# ventmon_t0_5e.net
KiCad netlist of a schematic drawn in EAGLE
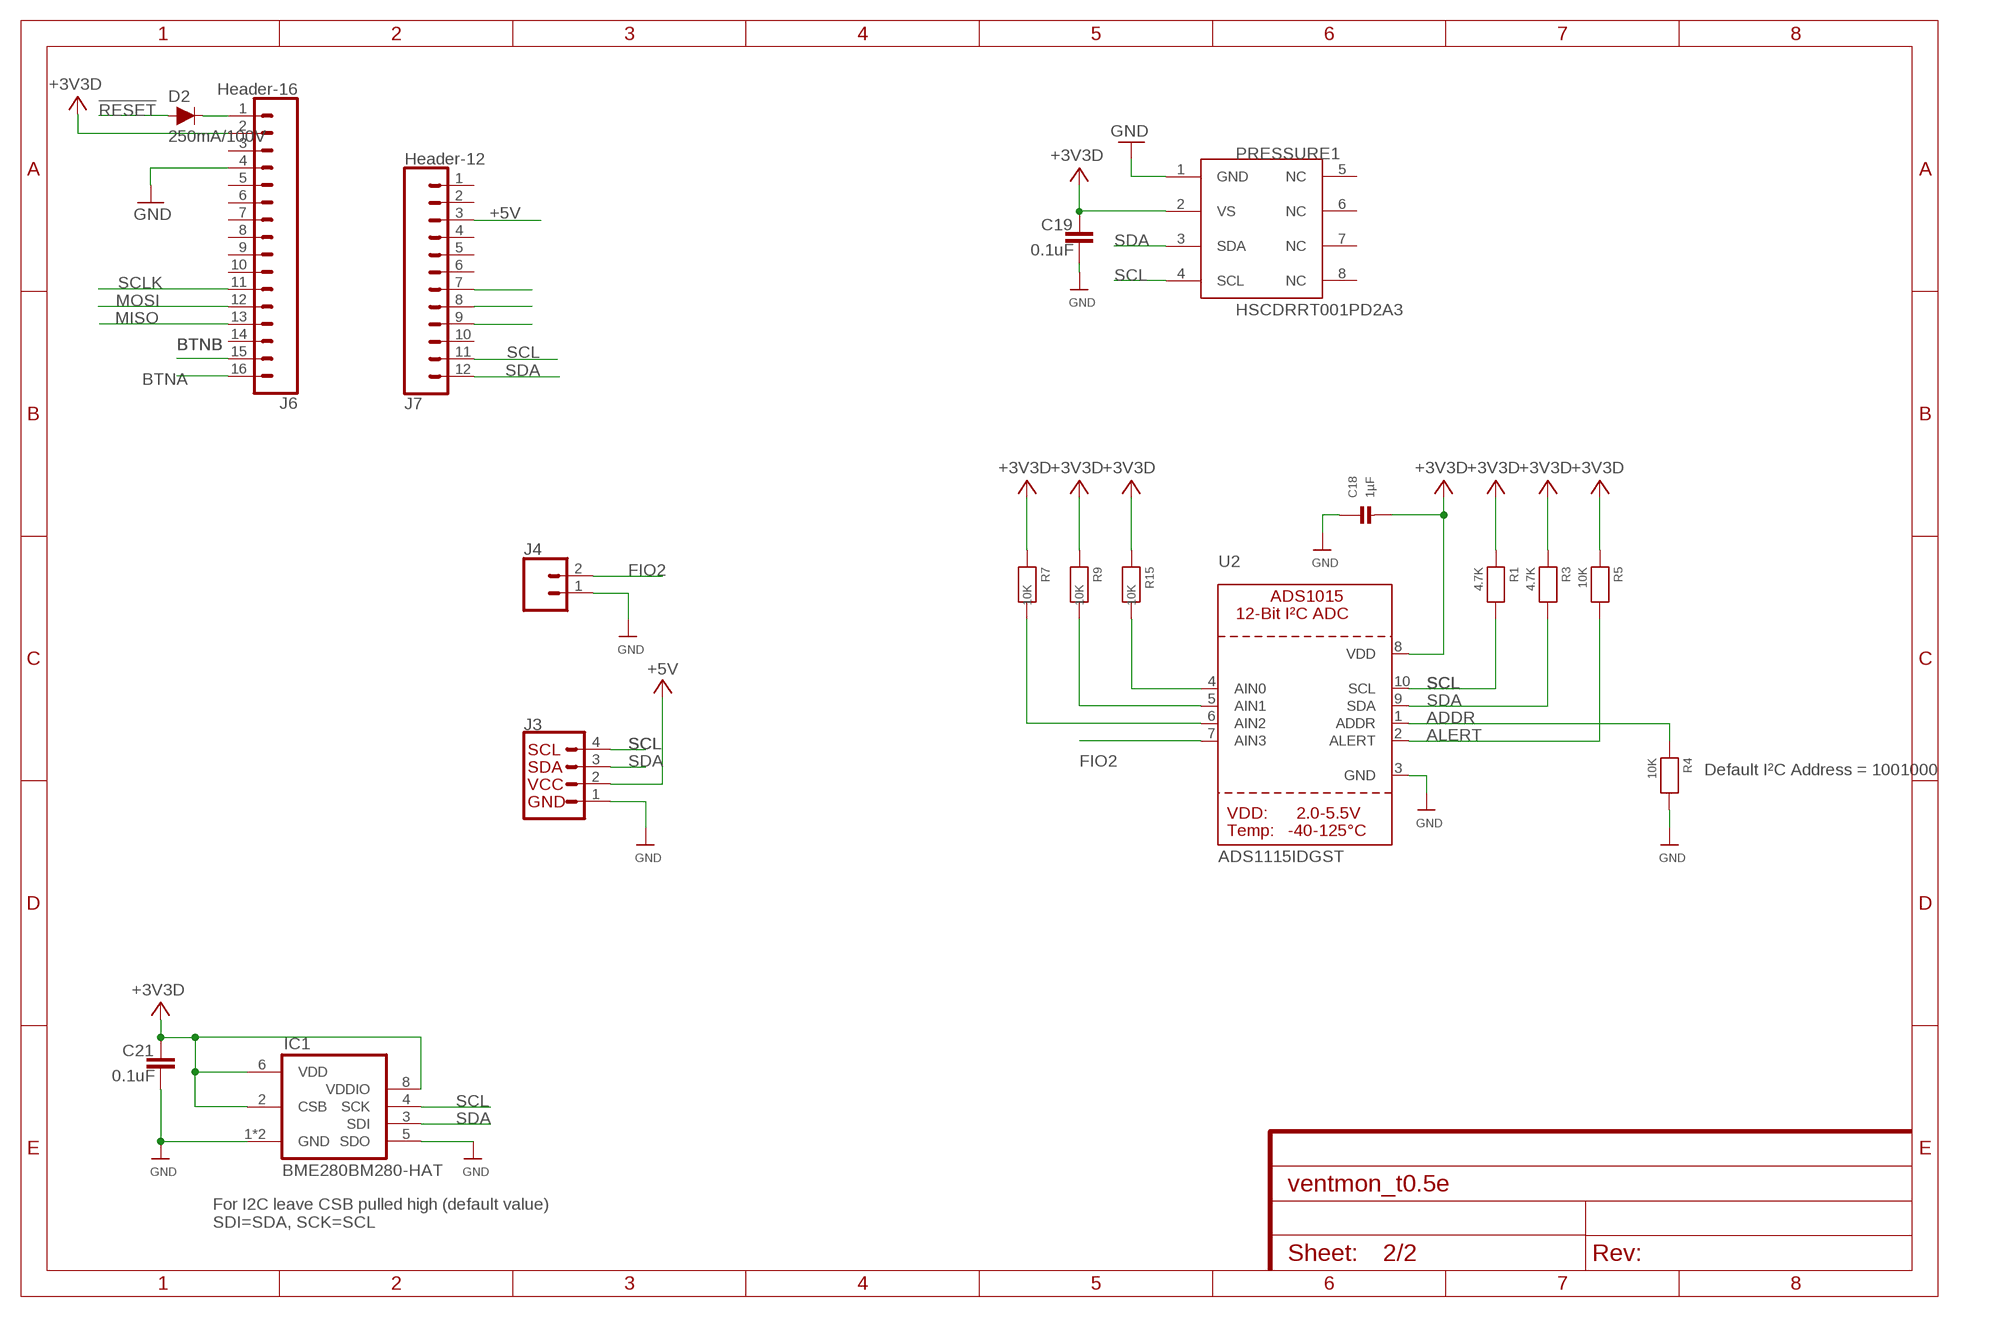
[diagram p0: schematic, sheet 2]

(export (version "E")
  (design (tool "Eeschema 10.0.6"))
  (components
    (comp (ref "C18")
      (value "1µF")
      (footprint "eagle-import:0603")
      (libsource (lib "eagle-import") (part "CAP_CERAMIC0603"))
    )
    (comp (ref "C19")
      (value "0.1uF")
      (footprint "eagle-import:C0402_B")
      (libsource (lib "eagle-import") (part "CAP_1"))
    )
    (comp (ref "C21")
      (value "0.1uF")
      (footprint "eagle-import:C0402_B")
      (libsource (lib "eagle-import") (part "CAP_1"))
    )
    (comp (ref "D2")
      (value "250mA/100V")
      (footprint "eagle-import:SOD-323")
      (libsource (lib "eagle-import") (part "DIODE-BAS16J"))
    )
    (comp (ref "IC1")
      (value "BME280BM280-HAT")
      (footprint "eagle-import:BME280-HAT")
      (libsource (lib "eagle-import") (part "BME280BM280-HAT"))
    )
    (comp (ref "J3")
      (value "QWIIC_CONNECTORJS-1MM")
      (footprint "eagle-import:1X04_1MM_RA")
      (libsource (lib "eagle-import") (part "QWIIC_CONNECTORJS-1MM"))
    )
    (comp (ref "J4")
      (value "CONN_02")
      (footprint "eagle-import:1X02")
      (libsource (lib "eagle-import") (part "CONN_02"))
    )
    (comp (ref "J6")
      (value "Header-16")
      (footprint "eagle-import:1X16")
      (libsource (lib "eagle-import") (part "CONN_16"))
    )
    (comp (ref "J7")
      (value "Header-12")
      (footprint "eagle-import:1X12")
      (libsource (lib "eagle-import") (part "CONN_12"))
    )
    (comp (ref "PRESSURE1")
      (value "HSCDRRT001PD2A3")
      (footprint "eagle-import:DIP1330W46P254L1000H616Q8B")
      (libsource (lib "eagle-import") (part "HSCDRRT001PD2A3"))
    )
    (comp (ref "R1")
      (value "4.7K")
      (footprint "eagle-import:0603")
      (libsource (lib "eagle-import") (part "RESISTOR0603"))
    )
    (comp (ref "R3")
      (value "4.7K")
      (footprint "eagle-import:0603")
      (libsource (lib "eagle-import") (part "RESISTOR0603"))
    )
    (comp (ref "R4")
      (value "10K")
      (footprint "eagle-import:0603")
      (libsource (lib "eagle-import") (part "RESISTOR0603"))
    )
    (comp (ref "R5")
      (value "10K")
      (footprint "eagle-import:0603")
      (libsource (lib "eagle-import") (part "RESISTOR0603"))
    )
    (comp (ref "R7")
      (value "10K")
      (footprint "eagle-import:0603")
      (libsource (lib "eagle-import") (part "RESISTOR0603"))
    )
    (comp (ref "R9")
      (value "10K")
      (footprint "eagle-import:0603")
      (libsource (lib "eagle-import") (part "RESISTOR0603"))
    )
    (comp (ref "R15")
      (value "10K")
      (footprint "eagle-import:0603")
      (libsource (lib "eagle-import") (part "RESISTOR0603"))
    )
    (comp (ref "U2")
      (value "ADS1115IDGST")
      (footprint "eagle-import:MSOP10")
      (libsource (lib "eagle-import") (part "ADC_ADS1015"))
    )
  )
  (nets
    (net (code "1") (name "+3V3") (class "Default")
      (node (ref "C18") (pin "2") (pinfunction "P$2_2") (pintype "passive"))
      (node (ref "C19") (pin "2") (pinfunction "P$2_2") (pintype "passive"))
      (node (ref "C21") (pin "2") (pinfunction "P$2_2") (pintype "passive"))
      (node (ref "IC1") (pin "2") (pinfunction "CSB_2") (pintype "input"))
      (node (ref "IC1") (pin "6") (pinfunction "VDD_6") (pintype "power_in"))
      (node (ref "IC1") (pin "8") (pinfunction "VDDIO_8") (pintype "power_in"))
      (node (ref "J6") (pin "2") (pinfunction "2_2") (pintype "passive"))
      (node (ref "PRESSURE1") (pin "2") (pinfunction "VS_2") (pintype "bidirectional"))
      (node (ref "R1") (pin "1") (pinfunction "1_1") (pintype "passive"))
      (node (ref "R15") (pin "1") (pinfunction "1_1") (pintype "passive"))
      (node (ref "R3") (pin "1") (pinfunction "1_1") (pintype "passive"))
      (node (ref "R5") (pin "1") (pinfunction "1_1") (pintype "passive"))
      (node (ref "R7") (pin "1") (pinfunction "1_1") (pintype "passive"))
      (node (ref "R9") (pin "1") (pinfunction "1_1") (pintype "passive"))
      (node (ref "U2") (pin "8") (pinfunction "VDD_8") (pintype "bidirectional"))
    )
    (net (code "2") (name "+5V") (class "Default")
      (node (ref "J3") (pin "2") (pinfunction "VCC_2") (pintype "power_in"))
      (node (ref "J7") (pin "3") (pinfunction "3_3") (pintype "passive"))
    )
    (net (code "3") (name "ADDR") (class "Default")
      (node (ref "R4") (pin "1") (pinfunction "1_1") (pintype "passive"))
      (node (ref "U2") (pin "1") (pinfunction "ADDR_1") (pintype "bidirectional"))
    )
    (net (code "4") (name "ALERT") (class "Default")
      (node (ref "R5") (pin "2") (pinfunction "2_2") (pintype "passive"))
      (node (ref "U2") (pin "2") (pinfunction "ALERT_2") (pintype "bidirectional"))
    )
    (net (code "5") (name "BTNA") (class "Default")
      (node (ref "J6") (pin "16") (pinfunction "16_16") (pintype "passive"))
    )
    (net (code "6") (name "BTNB") (class "Default")
      (node (ref "J6") (pin "15") (pinfunction "15_15") (pintype "passive"))
    )
    (net (code "7") (name "FIO2") (class "Default")
      (node (ref "J4") (pin "2") (pinfunction "2_2") (pintype "passive"))
      (node (ref "U2") (pin "7") (pinfunction "AIN3_7") (pintype "bidirectional"))
    )
    (net (code "8") (name "GND") (class "Default")
      (node (ref "C18") (pin "1") (pinfunction "P$1_1") (pintype "passive"))
      (node (ref "C19") (pin "1") (pinfunction "P$1_1") (pintype "passive"))
      (node (ref "C21") (pin "1") (pinfunction "P$1_1") (pintype "passive"))
      (node (ref "IC1") (pin "1") (pinfunction "GND_1") (pintype "power_in"))
      (node (ref "IC1") (pin "5") (pinfunction "SDO_5") (pintype "input"))
      (node (ref "IC1") (pin "7") (pinfunction "GND_7") (pintype "power_in"))
      (node (ref "J3") (pin "1") (pinfunction "GND_1") (pintype "power_in"))
      (node (ref "J4") (pin "1") (pinfunction "1_1") (pintype "passive"))
      (node (ref "J6") (pin "4") (pinfunction "4_4") (pintype "passive"))
      (node (ref "PRESSURE1") (pin "1") (pinfunction "GND_1") (pintype "bidirectional"))
      (node (ref "R4") (pin "2") (pinfunction "2_2") (pintype "passive"))
      (node (ref "U2") (pin "3") (pinfunction "GND_3") (pintype "bidirectional"))
    )
    (net (code "9") (name "MISO") (class "Default")
      (node (ref "J6") (pin "13") (pinfunction "13_13") (pintype "passive"))
    )
    (net (code "10") (name "MOSI") (class "Default")
      (node (ref "J6") (pin "12") (pinfunction "12_12") (pintype "passive"))
    )
    (net (code "11") (name "Net-(D2-PadC)") (class "Default")
      (node (ref "D2") (pin "C") (pinfunction "C_C") (pintype "passive"))
      (node (ref "J6") (pin "1") (pinfunction "1_1") (pintype "passive"))
    )
    (net (code "12") (name "Net-(U2-AIN0)") (class "Default")
      (node (ref "R15") (pin "2") (pinfunction "2_2") (pintype "passive"))
      (node (ref "U2") (pin "4") (pinfunction "AIN0_4") (pintype "bidirectional"))
    )
    (net (code "13") (name "Net-(U2-AIN1)") (class "Default")
      (node (ref "R9") (pin "2") (pinfunction "2_2") (pintype "passive"))
      (node (ref "U2") (pin "5") (pinfunction "AIN1_5") (pintype "bidirectional"))
    )
    (net (code "14") (name "Net-(U2-AIN2)") (class "Default")
      (node (ref "R7") (pin "2") (pinfunction "2_2") (pintype "passive"))
      (node (ref "U2") (pin "6") (pinfunction "AIN2_6") (pintype "bidirectional"))
    )
    (net (code "15") (name "SCL") (class "Default")
      (node (ref "IC1") (pin "4") (pinfunction "SCK_4") (pintype "bidirectional"))
      (node (ref "J3") (pin "4") (pinfunction "SCL_4") (pintype "passive"))
      (node (ref "J7") (pin "11") (pinfunction "11_11") (pintype "passive"))
      (node (ref "PRESSURE1") (pin "4") (pinfunction "SCL_4") (pintype "bidirectional"))
      (node (ref "R1") (pin "2") (pinfunction "2_2") (pintype "passive"))
      (node (ref "U2") (pin "10") (pinfunction "SCL_10") (pintype "bidirectional"))
    )
    (net (code "16") (name "SCLK") (class "Default")
      (node (ref "J6") (pin "11") (pinfunction "11_11") (pintype "passive"))
    )
    (net (code "17") (name "SDA") (class "Default")
      (node (ref "IC1") (pin "3") (pinfunction "SDI_3") (pintype "bidirectional"))
      (node (ref "J3") (pin "3") (pinfunction "SDA_3") (pintype "passive"))
      (node (ref "J7") (pin "12") (pinfunction "12_12") (pintype "passive"))
      (node (ref "PRESSURE1") (pin "3") (pinfunction "SDA_3") (pintype "bidirectional"))
      (node (ref "R3") (pin "2") (pinfunction "2_2") (pintype "passive"))
      (node (ref "U2") (pin "9") (pinfunction "SDA_9") (pintype "bidirectional"))
    )
    (net (code "18") (name "unconnected-(J6-Pad3)") (class "Default")
      (node (ref "J6") (pin "3") (pinfunction "3_3") (pintype "passive"))
    )
    (net (code "19") (name "unconnected-(J6-Pad5)") (class "Default")
      (node (ref "J6") (pin "5") (pinfunction "5_5") (pintype "passive"))
    )
    (net (code "20") (name "unconnected-(J6-Pad6)") (class "Default")
      (node (ref "J6") (pin "6") (pinfunction "6_6") (pintype "passive"))
    )
    (net (code "21") (name "unconnected-(J6-Pad7)") (class "Default")
      (node (ref "J6") (pin "7") (pinfunction "7_7") (pintype "passive"))
    )
    (net (code "22") (name "unconnected-(J6-Pad8)") (class "Default")
      (node (ref "J6") (pin "8") (pinfunction "8_8") (pintype "passive"))
    )
    (net (code "23") (name "unconnected-(J6-Pad9)") (class "Default")
      (node (ref "J6") (pin "9") (pinfunction "9_9") (pintype "passive"))
    )
    (net (code "24") (name "unconnected-(J6-Pad10)") (class "Default")
      (node (ref "J6") (pin "10") (pinfunction "10_10") (pintype "passive"))
    )
    (net (code "25") (name "unconnected-(J6-Pad14)") (class "Default")
      (node (ref "J6") (pin "14") (pinfunction "14_14") (pintype "passive"))
    )
    (net (code "26") (name "unconnected-(J7-Pad1)") (class "Default")
      (node (ref "J7") (pin "1") (pinfunction "1_1") (pintype "passive"))
    )
    (net (code "27") (name "unconnected-(J7-Pad2)") (class "Default")
      (node (ref "J7") (pin "2") (pinfunction "2_2") (pintype "passive"))
    )
    (net (code "28") (name "unconnected-(J7-Pad4)") (class "Default")
      (node (ref "J7") (pin "4") (pinfunction "4_4") (pintype "passive"))
    )
    (net (code "29") (name "unconnected-(J7-Pad5)") (class "Default")
      (node (ref "J7") (pin "5") (pinfunction "5_5") (pintype "passive"))
    )
    (net (code "30") (name "unconnected-(J7-Pad6)") (class "Default")
      (node (ref "J7") (pin "6") (pinfunction "6_6") (pintype "passive"))
    )
    (net (code "31") (name "unconnected-(J7-Pad7)") (class "Default")
      (node (ref "J7") (pin "7") (pinfunction "7_7") (pintype "passive"))
    )
    (net (code "32") (name "unconnected-(J7-Pad8)") (class "Default")
      (node (ref "J7") (pin "8") (pinfunction "8_8") (pintype "passive"))
    )
    (net (code "33") (name "unconnected-(J7-Pad9)") (class "Default")
      (node (ref "J7") (pin "9") (pinfunction "9_9") (pintype "passive"))
    )
    (net (code "34") (name "unconnected-(J7-Pad10)") (class "Default")
      (node (ref "J7") (pin "10") (pinfunction "10_10") (pintype "passive"))
    )
    (net (code "35") (name "unconnected-(PRESSURE1-NC-Pad5)") (class "Default")
      (node (ref "PRESSURE1") (pin "5") (pinfunction "NC_5") (pintype "bidirectional"))
    )
    (net (code "36") (name "unconnected-(PRESSURE1-NC-Pad6)") (class "Default")
      (node (ref "PRESSURE1") (pin "6") (pinfunction "NC_6") (pintype "bidirectional"))
    )
    (net (code "37") (name "unconnected-(PRESSURE1-NC-Pad7)") (class "Default")
      (node (ref "PRESSURE1") (pin "7") (pinfunction "NC_7") (pintype "bidirectional"))
    )
    (net (code "38") (name "unconnected-(PRESSURE1-NC-Pad8)") (class "Default")
      (node (ref "PRESSURE1") (pin "8") (pinfunction "NC_8") (pintype "bidirectional"))
    )
    (net (code "39") (name "~{RESET}") (class "Default")
      (node (ref "D2") (pin "A") (pinfunction "A_A") (pintype "passive"))
    )
  )
)
